# RAMPS_1_6_2.net
KiCad netlist of a schematic drawn in EAGLE
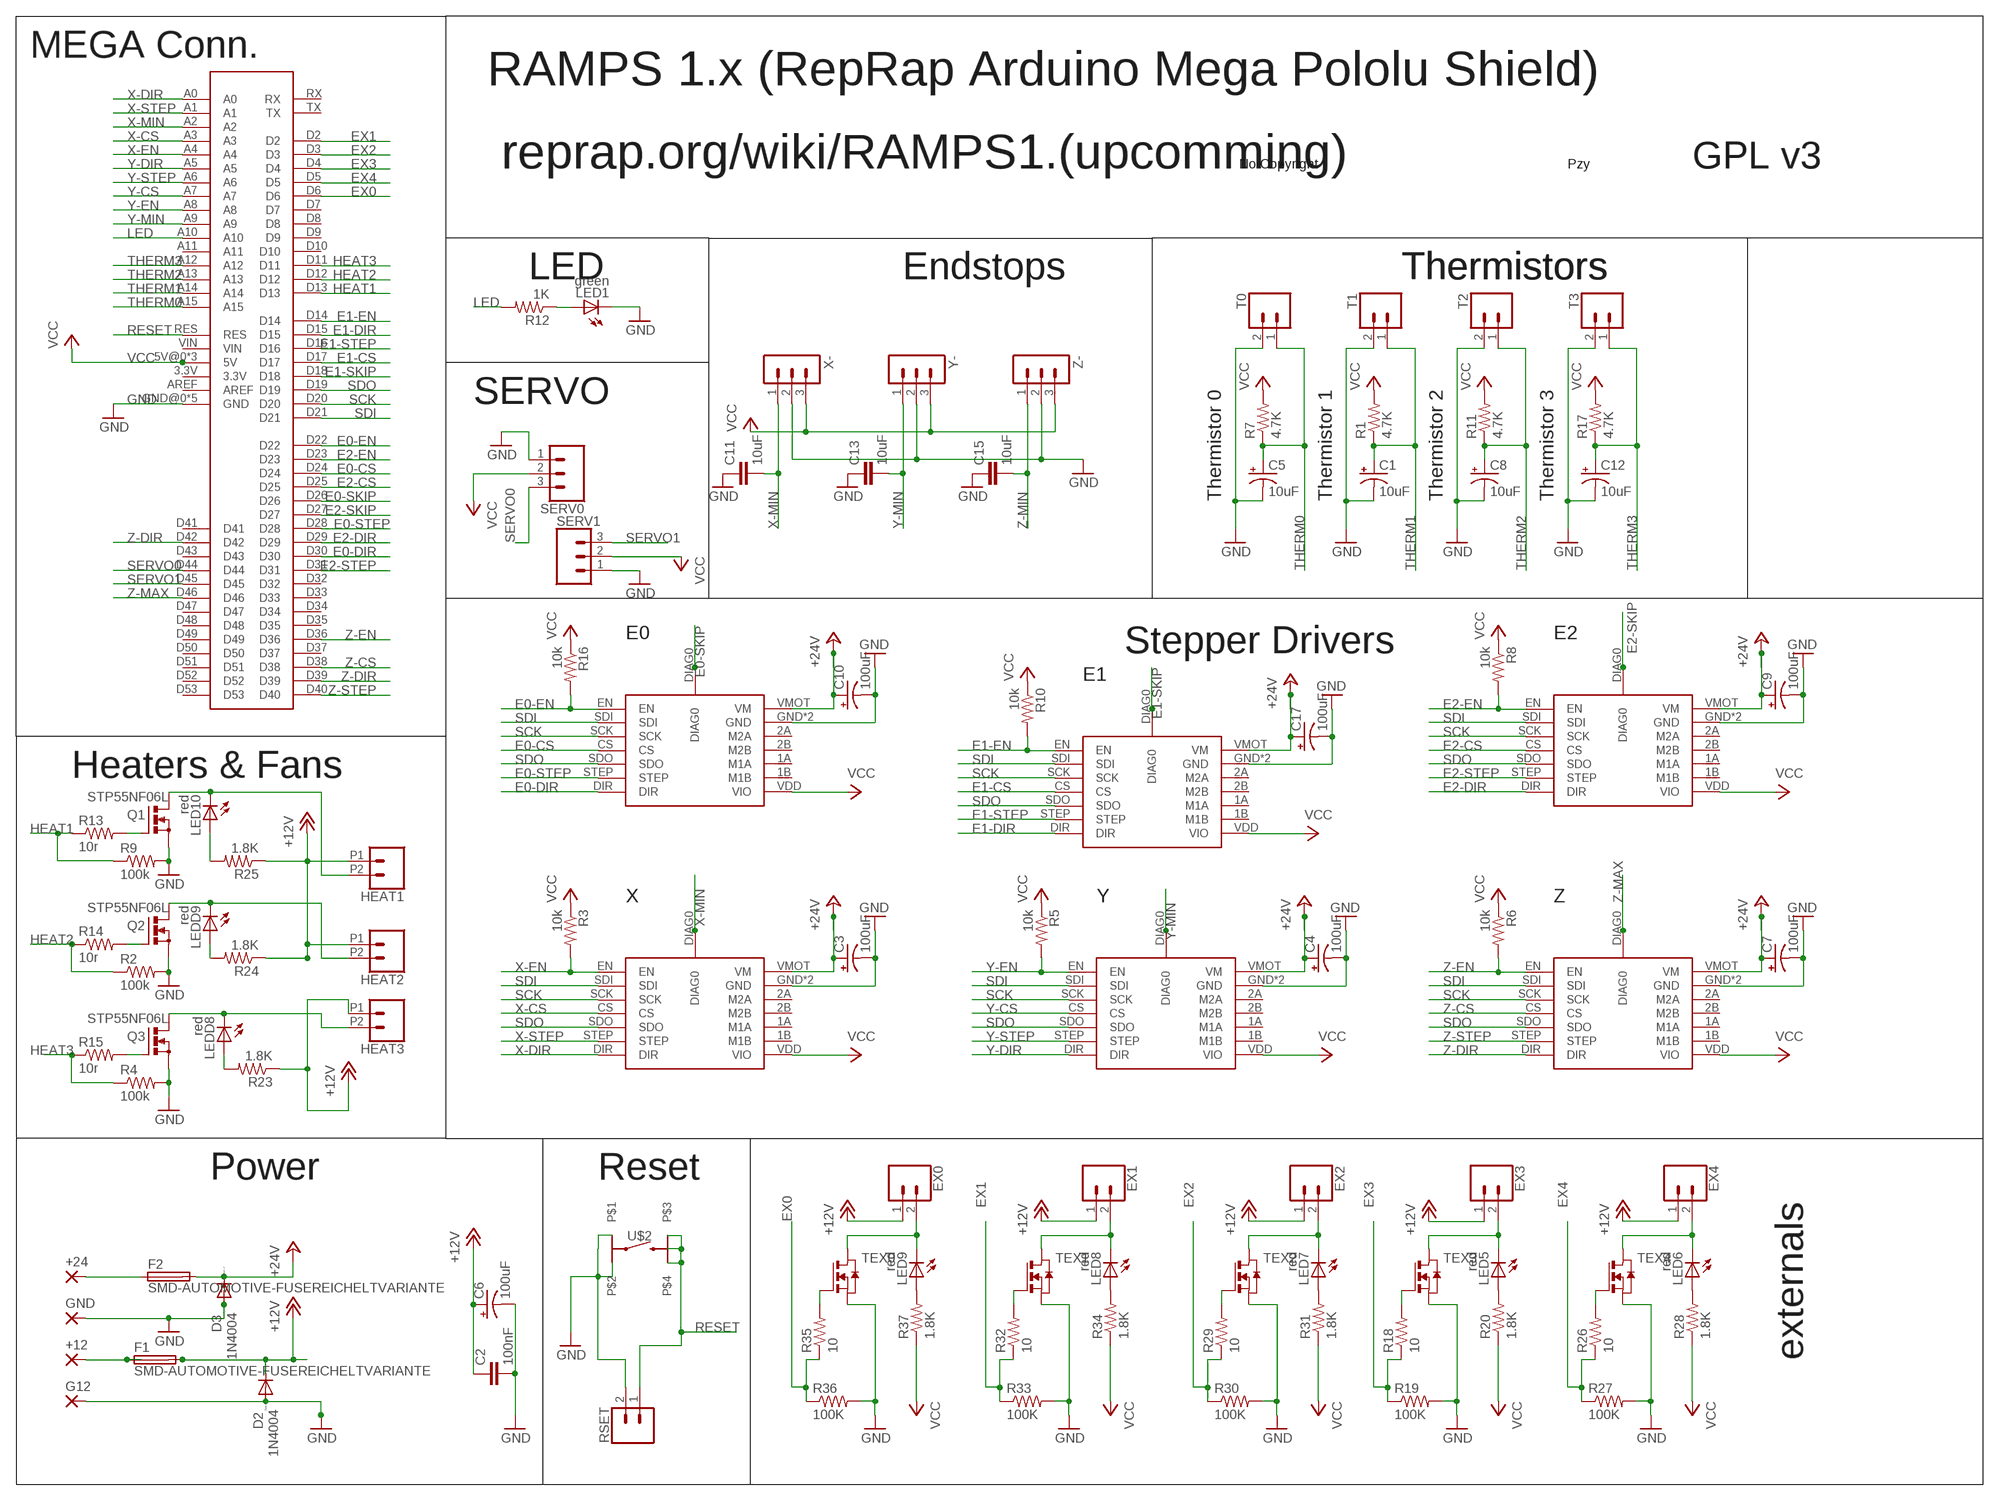
[diagram p0: schematic, sheet 1]

(export (version "E")
  (design (tool "Eeschema 10.0.6"))
  (components
    (comp (ref "+12")
      (value "2,15/1,0")
      (footprint "eagle-import:2,15_1,0")
      (libsource (lib "eagle-import") (part "2,15/1,0"))
    )
    (comp (ref "+24")
      (value "2,15/1,0")
      (footprint "eagle-import:2,15_1,0")
      (libsource (lib "eagle-import") (part "2,15/1,0"))
    )
    (comp (ref "C1")
      (value "10uF")
      (footprint "eagle-import:153CLV-0405")
      (libsource (lib "eagle-import") (part "CPOL-US153CLV-0405"))
    )
    (comp (ref "C2")
      (value "100nF")
      (footprint "eagle-import:C1206")
      (libsource (lib "eagle-import") (part "resistor_348_C-EUC1206"))
    )
    (comp (ref "C3")
      (value "100uF")
      (footprint "eagle-import:153CLV-0605")
      (libsource (lib "eagle-import") (part "CPOL-US153CLV-0605"))
    )
    (comp (ref "C4")
      (value "100uF")
      (footprint "eagle-import:153CLV-0605")
      (libsource (lib "eagle-import") (part "CPOL-US153CLV-0605"))
    )
    (comp (ref "C5")
      (value "10uF")
      (footprint "eagle-import:153CLV-0405")
      (libsource (lib "eagle-import") (part "CPOL-US153CLV-0405"))
    )
    (comp (ref "C6")
      (value "100uF")
      (footprint "eagle-import:153CLV-0605")
      (libsource (lib "eagle-import") (part "CPOL-US153CLV-0605"))
    )
    (comp (ref "C7")
      (value "100uF")
      (footprint "eagle-import:153CLV-0605")
      (libsource (lib "eagle-import") (part "CPOL-US153CLV-0605"))
    )
    (comp (ref "C8")
      (value "10uF")
      (footprint "eagle-import:153CLV-0405")
      (libsource (lib "eagle-import") (part "CPOL-US153CLV-0405"))
    )
    (comp (ref "C9")
      (value "100uF")
      (footprint "eagle-import:153CLV-0605")
      (libsource (lib "eagle-import") (part "CPOL-US153CLV-0605"))
    )
    (comp (ref "C10")
      (value "100uF")
      (footprint "eagle-import:153CLV-0605")
      (libsource (lib "eagle-import") (part "CPOL-US153CLV-0605"))
    )
    (comp (ref "C11")
      (value "10uF")
      (footprint "eagle-import:C1206")
      (libsource (lib "eagle-import") (part "C-EUC1206"))
    )
    (comp (ref "C12")
      (value "10uF")
      (footprint "eagle-import:153CLV-0405")
      (libsource (lib "eagle-import") (part "CPOL-US153CLV-0405"))
    )
    (comp (ref "C13")
      (value "10uF")
      (footprint "eagle-import:C1206")
      (libsource (lib "eagle-import") (part "C-EUC1206"))
    )
    (comp (ref "C15")
      (value "10uF")
      (footprint "eagle-import:C1206")
      (libsource (lib "eagle-import") (part "C-EUC1206"))
    )
    (comp (ref "C17")
      (value "100uF")
      (footprint "eagle-import:153CLV-0605")
      (libsource (lib "eagle-import") (part "CPOL-US153CLV-0605"))
    )
    (comp (ref "D2")
      (value "1N4004")
      (footprint "eagle-import:DO41-10")
      (libsource (lib "eagle-import") (part "1N4004"))
    )
    (comp (ref "D3")
      (value "1N4004")
      (footprint "eagle-import:DO41-10")
      (libsource (lib "eagle-import") (part "1N4004"))
    )
    (comp (ref "E0")
      (value "TMC2130DIAG")
      (footprint "eagle-import:TMC2130DIAG0")
      (libsource (lib "eagle-import") (part "TMC2130DIAG"))
    )
    (comp (ref "E1")
      (value "TMC2130DIAG")
      (footprint "eagle-import:TMC2130DIAG0")
      (libsource (lib "eagle-import") (part "TMC2130DIAG"))
    )
    (comp (ref "E2")
      (value "TMC2130DIAG")
      (footprint "eagle-import:TMC2130DIAG0")
      (libsource (lib "eagle-import") (part "TMC2130DIAG"))
    )
    (comp (ref "EX0")
      (value "CONN_02POLAR_LOCK")
      (footprint "eagle-import:MOLEX-1X2_LOCK")
      (fields (field (name "SPICEPREFIX") "B"))
      (libsource (lib "eagle-import") (part "CONN_02POLAR_LOCK"))
    )
    (comp (ref "EX1")
      (value "CONN_02POLAR_LOCK")
      (footprint "eagle-import:MOLEX-1X2_LOCK")
      (fields (field (name "SPICEPREFIX") "B"))
      (libsource (lib "eagle-import") (part "CONN_02POLAR_LOCK"))
    )
    (comp (ref "EX2")
      (value "CONN_02POLAR_LOCK")
      (footprint "eagle-import:MOLEX-1X2_LOCK")
      (fields (field (name "SPICEPREFIX") "B"))
      (libsource (lib "eagle-import") (part "CONN_02POLAR_LOCK"))
    )
    (comp (ref "EX3")
      (value "CONN_02POLAR_LOCK")
      (footprint "eagle-import:MOLEX-1X2_LOCK")
      (fields (field (name "SPICEPREFIX") "B"))
      (libsource (lib "eagle-import") (part "CONN_02POLAR_LOCK"))
    )
    (comp (ref "EX4")
      (value "CONN_02POLAR_LOCK")
      (footprint "eagle-import:MOLEX-1X2_LOCK")
      (fields (field (name "SPICEPREFIX") "B"))
      (libsource (lib "eagle-import") (part "CONN_02POLAR_LOCK"))
    )
    (comp (ref "F1")
      (value "SMD-AUTOMOTIVE-FUSEREICHELTVARIANTE")
      (footprint "eagle-import:RS-SMDFUSE")
      (libsource (lib "eagle-import") (part "SMD-AUTOMOTIVE-FUSEREICHELTVARIANTE"))
    )
    (comp (ref "F2")
      (value "SMD-AUTOMOTIVE-FUSEREICHELTVARIANTE")
      (footprint "eagle-import:RS-SMDFUSE")
      (libsource (lib "eagle-import") (part "SMD-AUTOMOTIVE-FUSEREICHELTVARIANTE"))
    )
    (comp (ref "G12")
      (value "2,15/1,0")
      (footprint "eagle-import:2,15_1,0")
      (libsource (lib "eagle-import") (part "2,15/1,0"))
    )
    (comp (ref "GND")
      (value "2,15/1,0")
      (footprint "eagle-import:2,15_1,0")
      (libsource (lib "eagle-import") (part "2,15/1,0"))
    )
    (comp (ref "HEAT1")
      (value "CONN_022.54MM_SCREWTERM")
      (footprint "eagle-import:1X02_2.54_SCREWTERM")
      (libsource (lib "eagle-import") (part "CONN_022.54MM_SCREWTERM"))
    )
    (comp (ref "HEAT2")
      (value "CONN_022.54MM_SCREWTERM")
      (footprint "eagle-import:1X02_2.54_SCREWTERM")
      (libsource (lib "eagle-import") (part "CONN_022.54MM_SCREWTERM"))
    )
    (comp (ref "HEAT3")
      (value "CONN_022.54MM_SCREWTERM")
      (footprint "eagle-import:1X02_2.54_SCREWTERM")
      (libsource (lib "eagle-import") (part "CONN_022.54MM_SCREWTERM"))
    )
    (comp (ref "LED1")
      (value "green")
      (footprint "eagle-import:CHIPLED_1206")
      (libsource (lib "eagle-import") (part "LEDCHIPLED_1206"))
    )
    (comp (ref "LED5")
      (value "red")
      (footprint "eagle-import:CHIPLED_1206")
      (fields (field (name "SPICEPREFIX") "L"))
      (libsource (lib "eagle-import") (part "LEDCHIPLED_1206"))
    )
    (comp (ref "LED6")
      (value "red")
      (footprint "eagle-import:CHIPLED_1206")
      (fields (field (name "SPICEPREFIX") "L"))
      (libsource (lib "eagle-import") (part "LEDCHIPLED_1206"))
    )
    (comp (ref "LED7")
      (value "red")
      (footprint "eagle-import:CHIPLED_1206")
      (fields (field (name "SPICEPREFIX") "L"))
      (libsource (lib "eagle-import") (part "LEDCHIPLED_1206"))
    )
    (comp (ref "LED8")
      (value "red")
      (footprint "eagle-import:CHIPLED_1206")
      (fields (field (name "SPICEPREFIX") "L"))
      (libsource (lib "eagle-import") (part "LEDCHIPLED_1206"))
    )
    (comp (ref "LED9")
      (value "red")
      (footprint "eagle-import:CHIPLED_1206")
      (fields (field (name "SPICEPREFIX") "L"))
      (libsource (lib "eagle-import") (part "LEDCHIPLED_1206"))
    )
    (comp (ref "LED10")
      (value "red")
      (footprint "eagle-import:CHIPLED_1206")
      (libsource (lib "eagle-import") (part "LEDCHIPLED_1206"))
    )
    (comp (ref "LEDD8")
      (value "red")
      (footprint "eagle-import:CHIPLED_1206")
      (libsource (lib "eagle-import") (part "LEDCHIPLED_1206"))
    )
    (comp (ref "LEDD9")
      (value "red")
      (footprint "eagle-import:CHIPLED_1206")
      (libsource (lib "eagle-import") (part "LEDCHIPLED_1206"))
    )
    (comp (ref "Q1")
      (value "STP55NF06L")
      (footprint "eagle-import:TO220BV")
      (libsource (lib "eagle-import") (part "IRF512"))
    )
    (comp (ref "Q2")
      (value "STP55NF06L")
      (footprint "eagle-import:TO220BV")
      (libsource (lib "eagle-import") (part "IRF512"))
    )
    (comp (ref "Q3")
      (value "STP55NF06L")
      (footprint "eagle-import:TO220BV")
      (libsource (lib "eagle-import") (part "IRF512"))
    )
    (comp (ref "R1")
      (value "4.7K")
      (footprint "eagle-import:R1206")
      (libsource (lib "eagle-import") (part "R-US_R1206"))
    )
    (comp (ref "R2")
      (value "100k")
      (footprint "eagle-import:R1206")
      (libsource (lib "eagle-import") (part "R-US_R1206"))
    )
    (comp (ref "R3")
      (value "10k")
      (footprint "eagle-import:R1206")
      (libsource (lib "eagle-import") (part "R-US_R1206"))
    )
    (comp (ref "R4")
      (value "100k")
      (footprint "eagle-import:R1206")
      (libsource (lib "eagle-import") (part "R-US_R1206"))
    )
    (comp (ref "R5")
      (value "10k")
      (footprint "eagle-import:R1206")
      (libsource (lib "eagle-import") (part "R-US_R1206"))
    )
    (comp (ref "R6")
      (value "10k")
      (footprint "eagle-import:R1206")
      (libsource (lib "eagle-import") (part "R-US_R1206"))
    )
    (comp (ref "R7")
      (value "4.7K")
      (footprint "eagle-import:R1206")
      (libsource (lib "eagle-import") (part "R-US_R1206"))
    )
    (comp (ref "R8")
      (value "10k")
      (footprint "eagle-import:R1206")
      (libsource (lib "eagle-import") (part "R-US_R1206"))
    )
    (comp (ref "R9")
      (value "100k")
      (footprint "eagle-import:R1206")
      (libsource (lib "eagle-import") (part "R-US_R1206"))
    )
    (comp (ref "R10")
      (value "10k")
      (footprint "eagle-import:R1206")
      (libsource (lib "eagle-import") (part "R-US_R1206"))
    )
    (comp (ref "R11")
      (value "4.7K")
      (footprint "eagle-import:R1206")
      (libsource (lib "eagle-import") (part "R-US_R1206"))
    )
    (comp (ref "R12")
      (value "1K")
      (footprint "eagle-import:R1206")
      (libsource (lib "eagle-import") (part "R-US_R1206"))
    )
    (comp (ref "R13")
      (value "10r")
      (footprint "eagle-import:R1206")
      (libsource (lib "eagle-import") (part "resistor_348_R-US_R1206"))
    )
    (comp (ref "R14")
      (value "10r")
      (footprint "eagle-import:R1206")
      (libsource (lib "eagle-import") (part "resistor_348_R-US_R1206"))
    )
    (comp (ref "R15")
      (value "10r")
      (footprint "eagle-import:R1206")
      (libsource (lib "eagle-import") (part "resistor_348_R-US_R1206"))
    )
    (comp (ref "R16")
      (value "10k")
      (footprint "eagle-import:R1206")
      (libsource (lib "eagle-import") (part "R-US_R1206"))
    )
    (comp (ref "R17")
      (value "4.7K")
      (footprint "eagle-import:R1206")
      (libsource (lib "eagle-import") (part "R-US_R1206"))
    )
    (comp (ref "R18")
      (value "10")
      (footprint "eagle-import:R1206")
      (fields (field (name "SPICEPREFIX") "R"))
      (libsource (lib "eagle-import") (part "resistor_348_R-US_R1206"))
    )
    (comp (ref "R19")
      (value "100K")
      (footprint "eagle-import:R1206")
      (fields (field (name "SPICEPREFIX") "L"))
      (libsource (lib "eagle-import") (part "resistor_348_R-US_R1206"))
    )
    (comp (ref "R20")
      (value "1.8K")
      (footprint "eagle-import:R1206")
      (fields (field (name "SPICEPREFIX") "R"))
      (libsource (lib "eagle-import") (part "resistor_348_R-US_R1206"))
    )
    (comp (ref "R23")
      (value "1.8K")
      (footprint "eagle-import:R1206")
      (libsource (lib "eagle-import") (part "R-US_R1206"))
    )
    (comp (ref "R24")
      (value "1.8K")
      (footprint "eagle-import:R1206")
      (libsource (lib "eagle-import") (part "R-US_R1206"))
    )
    (comp (ref "R25")
      (value "1.8K")
      (footprint "eagle-import:R1206")
      (libsource (lib "eagle-import") (part "R-US_R1206"))
    )
    (comp (ref "R26")
      (value "10")
      (footprint "eagle-import:R1206")
      (fields (field (name "SPICEPREFIX") "R"))
      (libsource (lib "eagle-import") (part "resistor_348_R-US_R1206"))
    )
    (comp (ref "R27")
      (value "100K")
      (footprint "eagle-import:R1206")
      (fields (field (name "SPICEPREFIX") "R"))
      (libsource (lib "eagle-import") (part "resistor_348_R-US_R1206"))
    )
    (comp (ref "R28")
      (value "1.8K")
      (footprint "eagle-import:R1206")
      (fields (field (name "SPICEPREFIX") "R"))
      (libsource (lib "eagle-import") (part "resistor_348_R-US_R1206"))
    )
    (comp (ref "R29")
      (value "10")
      (footprint "eagle-import:R1206")
      (fields (field (name "SPICEPREFIX") "R"))
      (libsource (lib "eagle-import") (part "resistor_348_R-US_R1206"))
    )
    (comp (ref "R30")
      (value "100K")
      (footprint "eagle-import:R1206")
      (fields (field (name "SPICEPREFIX") "R"))
      (libsource (lib "eagle-import") (part "resistor_348_R-US_R1206"))
    )
    (comp (ref "R31")
      (value "1.8K")
      (footprint "eagle-import:R1206")
      (fields (field (name "SPICEPREFIX") "R"))
      (libsource (lib "eagle-import") (part "resistor_348_R-US_R1206"))
    )
    (comp (ref "R32")
      (value "10")
      (footprint "eagle-import:R1206")
      (fields (field (name "SPICEPREFIX") "R"))
      (libsource (lib "eagle-import") (part "resistor_348_R-US_R1206"))
    )
    (comp (ref "R33")
      (value "100K")
      (footprint "eagle-import:R1206")
      (fields (field (name "SPICEPREFIX") "R"))
      (libsource (lib "eagle-import") (part "resistor_348_R-US_R1206"))
    )
    (comp (ref "R34")
      (value "1.8K")
      (footprint "eagle-import:R1206")
      (fields (field (name "SPICEPREFIX") "R"))
      (libsource (lib "eagle-import") (part "resistor_348_R-US_R1206"))
    )
    (comp (ref "R35")
      (value "10")
      (footprint "eagle-import:R1206")
      (fields (field (name "SPICEPREFIX") "R"))
      (libsource (lib "eagle-import") (part "resistor_348_R-US_R1206"))
    )
    (comp (ref "R36")
      (value "100K")
      (footprint "eagle-import:R1206")
      (fields (field (name "SPICEPREFIX") "R"))
      (libsource (lib "eagle-import") (part "resistor_348_R-US_R1206"))
    )
    (comp (ref "R37")
      (value "1.8K")
      (footprint "eagle-import:R1206")
      (fields (field (name "SPICEPREFIX") "R"))
      (libsource (lib "eagle-import") (part "resistor_348_R-US_R1206"))
    )
    (comp (ref "RSET")
      (value "CONN_02POLAR_LOCK")
      (footprint "eagle-import:MOLEX-1X2_LOCK")
      (fields (field (name "SPICEPREFIX") "B"))
      (libsource (lib "eagle-import") (part "CONN_02POLAR_LOCK"))
    )
    (comp (ref "SERV0")
      (value "CONN_03")
      (footprint "eagle-import:1X03")
      (libsource (lib "eagle-import") (part "CONN_03"))
    )
    (comp (ref "SERV1")
      (value "CONN_03")
      (footprint "eagle-import:1X03")
      (libsource (lib "eagle-import") (part "CONN_03"))
    )
    (comp (ref "T0")
      (value "CONN_02LOCK")
      (footprint "eagle-import:1X02_LOCK")
      (libsource (lib "eagle-import") (part "CONN_02LOCK"))
    )
    (comp (ref "T1")
      (value "CONN_02LOCK")
      (footprint "eagle-import:1X02_LOCK")
      (libsource (lib "eagle-import") (part "CONN_02LOCK"))
    )
    (comp (ref "T2")
      (value "CONN_02LOCK")
      (footprint "eagle-import:1X02_LOCK")
      (libsource (lib "eagle-import") (part "CONN_02LOCK"))
    )
    (comp (ref "T3")
      (value "CONN_02LOCK")
      (footprint "eagle-import:1X02_LOCK")
      (libsource (lib "eagle-import") (part "CONN_02LOCK"))
    )
    (comp (ref "TEX0")
      (value "NMOSSOT223")
      (footprint "eagle-import:SOT223")
      (fields (field (name "SPICEPREFIX") "J"))
      (libsource (lib "eagle-import") (part "NMOSSOT223"))
    )
    (comp (ref "TEX1")
      (value "NMOSSOT223")
      (footprint "eagle-import:SOT223")
      (fields (field (name "SPICEPREFIX") "J"))
      (libsource (lib "eagle-import") (part "NMOSSOT223"))
    )
    (comp (ref "TEX2")
      (value "NMOSSOT223")
      (footprint "eagle-import:SOT223")
      (fields (field (name "SPICEPREFIX") "J"))
      (libsource (lib "eagle-import") (part "NMOSSOT223"))
    )
    (comp (ref "TEX3")
      (value "NMOSSOT223")
      (footprint "eagle-import:SOT223")
      (fields (field (name "SPICEPREFIX") "J"))
      (libsource (lib "eagle-import") (part "NMOSSOT223"))
    )
    (comp (ref "TEX4")
      (value "NMOSSOT223")
      (footprint "eagle-import:SOT223")
      (fields (field (name "SPICEPREFIX") "J"))
      (libsource (lib "eagle-import") (part "NMOSSOT223"))
    )
    (comp (ref "U$1")
      (value "ARDUINOSHIELD")
      (footprint "eagle-import:REPRAPJR_ARDUINO_MEGA_SHIELD")
      (libsource (lib "eagle-import") (part "ARDUINOSHIELD"))
    )
    (comp (ref "U$2")
      (value "RS-TASTER")
      (footprint "eagle-import:RS-SWITCH")
      (libsource (lib "eagle-import") (part "RS-TASTER"))
    )
    (comp (ref "X")
      (value "TMC2130DIAG")
      (footprint "eagle-import:TMC2130DIAG0")
      (libsource (lib "eagle-import") (part "TMC2130DIAG"))
    )
    (comp (ref "X-")
      (value "3PIN-HEADER")
      (footprint "eagle-import:3PIN-HEADER")
      (libsource (lib "eagle-import") (part "3PIN-HEADER"))
    )
    (comp (ref "Y")
      (value "TMC2130DIAG")
      (footprint "eagle-import:TMC2130DIAG0")
      (libsource (lib "eagle-import") (part "TMC2130DIAG"))
    )
    (comp (ref "Y-")
      (value "3PIN-HEADER")
      (footprint "eagle-import:3PIN-HEADER")
      (libsource (lib "eagle-import") (part "3PIN-HEADER"))
    )
    (comp (ref "Z")
      (value "TMC2130DIAG")
      (footprint "eagle-import:TMC2130DIAG0")
      (libsource (lib "eagle-import") (part "TMC2130DIAG"))
    )
    (comp (ref "Z-")
      (value "3PIN-HEADER")
      (footprint "eagle-import:3PIN-HEADER")
      (libsource (lib "eagle-import") (part "3PIN-HEADER"))
    )
  )
  (nets
    (net (code "1") (name "+12V") (class "Default")
      (node (ref "C2") (pin "1") (pinfunction "1_1") (pintype "passive"))
      (node (ref "C6") (pin "+") (pinfunction "+_+") (pintype "passive"))
      (node (ref "D2") (pin "C") (pinfunction "C_C") (pintype "passive"))
      (node (ref "EX0") (pin "1") (pinfunction "1_1") (pintype "passive"))
      (node (ref "EX1") (pin "1") (pinfunction "1_1") (pintype "passive"))
      (node (ref "EX2") (pin "1") (pinfunction "1_1") (pintype "passive"))
      (node (ref "EX3") (pin "1") (pinfunction "1_1") (pintype "passive"))
      (node (ref "EX4") (pin "1") (pinfunction "1_1") (pintype "passive"))
      (node (ref "F1") (pin "P$5") (pinfunction "2_P$5") (pintype "passive"))
      (node (ref "F1") (pin "P$6") (pinfunction "2_P$6") (pintype "passive"))
      (node (ref "F1") (pin "P$7") (pinfunction "2_P$7") (pintype "passive"))
      (node (ref "F1") (pin "P$8") (pinfunction "2_P$8") (pintype "passive"))
      (node (ref "HEAT1") (pin "P1") (pinfunction "1_P1") (pintype "passive"))
      (node (ref "HEAT2") (pin "P1") (pinfunction "1_P1") (pintype "passive"))
      (node (ref "HEAT3") (pin "P1") (pinfunction "1_P1") (pintype "passive"))
      (node (ref "R23") (pin "1") (pinfunction "1_1") (pintype "passive"))
      (node (ref "R24") (pin "1") (pinfunction "1_1") (pintype "passive"))
      (node (ref "R25") (pin "1") (pinfunction "1_1") (pintype "passive"))
    )
    (net (code "2") (name "+24V") (class "Default")
      (node (ref "C10") (pin "+") (pinfunction "+_+") (pintype "passive"))
      (node (ref "C17") (pin "+") (pinfunction "+_+") (pintype "passive"))
      (node (ref "C3") (pin "+") (pinfunction "+_+") (pintype "passive"))
      (node (ref "C4") (pin "+") (pinfunction "+_+") (pintype "passive"))
      (node (ref "C7") (pin "+") (pinfunction "+_+") (pintype "passive"))
      (node (ref "C9") (pin "+") (pinfunction "+_+") (pintype "passive"))
      (node (ref "D3") (pin "C") (pinfunction "C_C") (pintype "passive"))
      (node (ref "E0") (pin "VMOT") (pinfunction "VM_VMOT") (pintype "bidirectional"))
      (node (ref "E1") (pin "VMOT") (pinfunction "VM_VMOT") (pintype "bidirectional"))
      (node (ref "E2") (pin "VMOT") (pinfunction "VM_VMOT") (pintype "bidirectional"))
      (node (ref "F2") (pin "P$5") (pinfunction "2_P$5") (pintype "passive"))
      (node (ref "F2") (pin "P$6") (pinfunction "2_P$6") (pintype "passive"))
      (node (ref "F2") (pin "P$7") (pinfunction "2_P$7") (pintype "passive"))
      (node (ref "F2") (pin "P$8") (pinfunction "2_P$8") (pintype "passive"))
      (node (ref "X") (pin "VMOT") (pinfunction "VM_VMOT") (pintype "bidirectional"))
      (node (ref "Y") (pin "VMOT") (pinfunction "VM_VMOT") (pintype "bidirectional"))
      (node (ref "Z") (pin "VMOT") (pinfunction "VM_VMOT") (pintype "bidirectional"))
    )
    (net (code "3") (name "/3.3V") (class "Default")
      (node (ref "U$1") (pin "3.3V") (pinfunction "3.3V_3.3V") (pintype "power_in"))
    )
    (net (code "4") (name "/AREF") (class "Default")
      (node (ref "U$1") (pin "AREF") (pinfunction "AREF_AREF") (pintype "power_in"))
    )
    (net (code "5") (name "/E0-CS") (class "Default")
      (node (ref "E0") (pin "CS") (pinfunction "CS_CS") (pintype "bidirectional"))
      (node (ref "U$1") (pin "D24") (pinfunction "D24_D24") (pintype "bidirectional"))
    )
    (net (code "6") (name "/E0-DIR") (class "Default")
      (node (ref "E0") (pin "DIR") (pinfunction "DIR_DIR") (pintype "bidirectional"))
      (node (ref "U$1") (pin "D30") (pinfunction "D30_D30") (pintype "bidirectional"))
    )
    (net (code "7") (name "/E0-EN") (class "Default")
      (node (ref "E0") (pin "EN") (pinfunction "EN_EN") (pintype "bidirectional"))
      (node (ref "R16") (pin "2") (pinfunction "2_2") (pintype "passive"))
      (node (ref "U$1") (pin "D22") (pinfunction "D22_D22") (pintype "bidirectional"))
    )
    (net (code "8") (name "/E0-SKIP") (class "Default")
      (node (ref "E0") (pin "DIAG0") (pinfunction "DIAG0_DIAG0") (pintype "bidirectional"))
      (node (ref "U$1") (pin "D26") (pinfunction "D26_D26") (pintype "bidirectional"))
    )
    (net (code "9") (name "/E0-STEP") (class "Default")
      (node (ref "E0") (pin "STEP") (pinfunction "STEP_STEP") (pintype "bidirectional"))
      (node (ref "U$1") (pin "D28") (pinfunction "D28_D28") (pintype "bidirectional"))
    )
    (net (code "10") (name "/E1-CS") (class "Default")
      (node (ref "E1") (pin "CS") (pinfunction "CS_CS") (pintype "bidirectional"))
      (node (ref "U$1") (pin "D17") (pinfunction "D17_D17") (pintype "bidirectional"))
    )
    (net (code "11") (name "/E1-DIR") (class "Default")
      (node (ref "E1") (pin "DIR") (pinfunction "DIR_DIR") (pintype "bidirectional"))
      (node (ref "U$1") (pin "D15") (pinfunction "D15_D15") (pintype "bidirectional"))
    )
    (net (code "12") (name "/E1-EN") (class "Default")
      (node (ref "E1") (pin "EN") (pinfunction "EN_EN") (pintype "bidirectional"))
      (node (ref "R10") (pin "2") (pinfunction "2_2") (pintype "passive"))
      (node (ref "U$1") (pin "D14") (pinfunction "D14_D14") (pintype "bidirectional"))
    )
    (net (code "13") (name "/E1-SKIP") (class "Default")
      (node (ref "E1") (pin "DIAG0") (pinfunction "DIAG0_DIAG0") (pintype "bidirectional"))
      (node (ref "U$1") (pin "D18") (pinfunction "D18_D18") (pintype "bidirectional"))
    )
    (net (code "14") (name "/E1-STEP") (class "Default")
      (node (ref "E1") (pin "STEP") (pinfunction "STEP_STEP") (pintype "bidirectional"))
      (node (ref "U$1") (pin "D16") (pinfunction "D16_D16") (pintype "bidirectional"))
    )
    (net (code "15") (name "/E2-CS") (class "Default")
      (node (ref "E2") (pin "CS") (pinfunction "CS_CS") (pintype "bidirectional"))
      (node (ref "U$1") (pin "D25") (pinfunction "D25_D25") (pintype "bidirectional"))
    )
    (net (code "16") (name "/E2-DIR") (class "Default")
      (node (ref "E2") (pin "DIR") (pinfunction "DIR_DIR") (pintype "bidirectional"))
      (node (ref "U$1") (pin "D29") (pinfunction "D29_D29") (pintype "bidirectional"))
    )
    (net (code "17") (name "/E2-EN") (class "Default")
      (node (ref "E2") (pin "EN") (pinfunction "EN_EN") (pintype "bidirectional"))
      (node (ref "R8") (pin "2") (pinfunction "2_2") (pintype "passive"))
      (node (ref "U$1") (pin "D23") (pinfunction "D23_D23") (pintype "bidirectional"))
    )
    (net (code "18") (name "/E2-SKIP") (class "Default")
      (node (ref "E2") (pin "DIAG0") (pinfunction "DIAG0_DIAG0") (pintype "bidirectional"))
      (node (ref "U$1") (pin "D27") (pinfunction "D27_D27") (pintype "bidirectional"))
    )
    (net (code "19") (name "/E2-STEP") (class "Default")
      (node (ref "E2") (pin "STEP") (pinfunction "STEP_STEP") (pintype "bidirectional"))
      (node (ref "U$1") (pin "D31") (pinfunction "D31_D31") (pintype "bidirectional"))
    )
    (net (code "20") (name "/EX0") (class "Default")
      (node (ref "R35") (pin "1") (pinfunction "1_1") (pintype "passive"))
      (node (ref "R36") (pin "1") (pinfunction "1_1") (pintype "passive"))
      (node (ref "U$1") (pin "D6") (pinfunction "D6_D6") (pintype "bidirectional"))
    )
    (net (code "21") (name "/EX1") (class "Default")
      (node (ref "R32") (pin "1") (pinfunction "1_1") (pintype "passive"))
      (node (ref "R33") (pin "1") (pinfunction "1_1") (pintype "passive"))
      (node (ref "U$1") (pin "D2") (pinfunction "D2_D2") (pintype "bidirectional"))
    )
    (net (code "22") (name "/EX2") (class "Default")
      (node (ref "R29") (pin "1") (pinfunction "1_1") (pintype "passive"))
      (node (ref "R30") (pin "1") (pinfunction "1_1") (pintype "passive"))
      (node (ref "U$1") (pin "D3") (pinfunction "D3_D3") (pintype "bidirectional"))
    )
    (net (code "23") (name "/EX3") (class "Default")
      (node (ref "R18") (pin "1") (pinfunction "1_1") (pintype "passive"))
      (node (ref "R19") (pin "1") (pinfunction "1_1") (pintype "passive"))
      (node (ref "U$1") (pin "D4") (pinfunction "D4_D4") (pintype "bidirectional"))
    )
    (net (code "24") (name "/EX4") (class "Default")
      (node (ref "R26") (pin "1") (pinfunction "1_1") (pintype "passive"))
      (node (ref "R27") (pin "1") (pinfunction "1_1") (pintype "passive"))
      (node (ref "U$1") (pin "D5") (pinfunction "D5_D5") (pintype "bidirectional"))
    )
    (net (code "25") (name "/HEAT1") (class "Default")
      (node (ref "R13") (pin "1") (pinfunction "1_1") (pintype "passive"))
      (node (ref "R9") (pin "1") (pinfunction "1_1") (pintype "passive"))
      (node (ref "U$1") (pin "D13") (pinfunction "D13_D13") (pintype "bidirectional"))
    )
    (net (code "26") (name "/HEAT2") (class "Default")
      (node (ref "R14") (pin "1") (pinfunction "1_1") (pintype "passive"))
      (node (ref "R2") (pin "1") (pinfunction "1_1") (pintype "passive"))
      (node (ref "U$1") (pin "D12") (pinfunction "D12_D12") (pintype "bidirectional"))
    )
    (net (code "27") (name "/HEAT3") (class "Default")
      (node (ref "R15") (pin "1") (pinfunction "1_1") (pintype "passive"))
      (node (ref "R4") (pin "1") (pinfunction "1_1") (pintype "passive"))
      (node (ref "U$1") (pin "D11") (pinfunction "D11_D11") (pintype "bidirectional"))
    )
    (net (code "28") (name "/LED") (class "Default")
      (node (ref "R12") (pin "2") (pinfunction "2_2") (pintype "passive"))
      (node (ref "U$1") (pin "A10") (pinfunction "A10_A10") (pintype "bidirectional"))
    )
    (net (code "29") (name "/RESET") (class "Default")
      (node (ref "RSET") (pin "1") (pinfunction "1_1") (pintype "passive"))
      (node (ref "U$1") (pin "RES") (pinfunction "RES_RES") (pintype "bidirectional"))
      (node (ref "U$2") (pin "P$3") (pinfunction "P$3_P$3") (pintype "bidirectional"))
      (node (ref "U$2") (pin "P$4") (pinfunction "P$4_P$4") (pintype "bidirectional"))
    )
    (net (code "30") (name "/SCK") (class "Default")
      (node (ref "E0") (pin "SCK") (pinfunction "SCK_SCK") (pintype "bidirectional"))
      (node (ref "E1") (pin "SCK") (pinfunction "SCK_SCK") (pintype "bidirectional"))
      (node (ref "E2") (pin "SCK") (pinfunction "SCK_SCK") (pintype "bidirectional"))
      (node (ref "U$1") (pin "D20") (pinfunction "D20_D20") (pintype "bidirectional"))
      (node (ref "X") (pin "SCK") (pinfunction "SCK_SCK") (pintype "bidirectional"))
      (node (ref "Y") (pin "SCK") (pinfunction "SCK_SCK") (pintype "bidirectional"))
      (node (ref "Z") (pin "SCK") (pinfunction "SCK_SCK") (pintype "bidirectional"))
    )
    (net (code "31") (name "/SDI") (class "Default")
      (node (ref "E0") (pin "SDI") (pinfunction "SDI_SDI") (pintype "bidirectional"))
      (node (ref "E1") (pin "SDI") (pinfunction "SDI_SDI") (pintype "bidirectional"))
      (node (ref "E2") (pin "SDI") (pinfunction "SDI_SDI") (pintype "bidirectional"))
      (node (ref "U$1") (pin "D21") (pinfunction "D21_D21") (pintype "bidirectional"))
      (node (ref "X") (pin "SDI") (pinfunction "SDI_SDI") (pintype "bidirectional"))
      (node (ref "Y") (pin "SDI") (pinfunction "SDI_SDI") (pintype "bidirectional"))
      (node (ref "Z") (pin "SDI") (pinfunction "SDI_SDI") (pintype "bidirectional"))
    )
    (net (code "32") (name "/SDO") (class "Default")
      (node (ref "E0") (pin "SDO") (pinfunction "SDO_SDO") (pintype "bidirectional"))
      (node (ref "E1") (pin "SDO") (pinfunction "SDO_SDO") (pintype "bidirectional"))
      (node (ref "E2") (pin "SDO") (pinfunction "SDO_SDO") (pintype "bidirectional"))
      (node (ref "U$1") (pin "D19") (pinfunction "D19_D19") (pintype "bidirectional"))
      (node (ref "X") (pin "SDO") (pinfunction "SDO_SDO") (pintype "bidirectional"))
      (node (ref "Y") (pin "SDO") (pinfunction "SDO_SDO") (pintype "bidirectional"))
      (node (ref "Z") (pin "SDO") (pinfunction "SDO_SDO") (pintype "bidirectional"))
    )
    (net (code "33") (name "/SERVO0") (class "Default")
      (node (ref "SERV0") (pin "3") (pinfunction "3_3") (pintype "passive"))
      (node (ref "U$1") (pin "D44") (pinfunction "D44_D44") (pintype "bidirectional"))
    )
    (net (code "34") (name "/SERVO1") (class "Default")
      (node (ref "SERV1") (pin "3") (pinfunction "3_3") (pintype "passive"))
      (node (ref "U$1") (pin "D45") (pinfunction "D45_D45") (pintype "bidirectional"))
    )
    (net (code "35") (name "/THERM0") (class "Default")
      (node (ref "C5") (pin "+") (pinfunction "+_+") (pintype "passive"))
      (node (ref "R7") (pin "1") (pinfunction "1_1") (pintype "passive"))
      (node (ref "T0") (pin "1") (pinfunction "1_1") (pintype "passive"))
      (node (ref "U$1") (pin "A15") (pinfunction "A15_A15") (pintype "bidirectional"))
    )
    (net (code "36") (name "/THERM1") (class "Default")
      (node (ref "C1") (pin "+") (pinfunction "+_+") (pintype "passive"))
      (node (ref "R1") (pin "1") (pinfunction "1_1") (pintype "passive"))
      (node (ref "T1") (pin "1") (pinfunction "1_1") (pintype "passive"))
      (node (ref "U$1") (pin "A14") (pinfunction "A14_A14") (pintype "bidirectional"))
    )
    (net (code "37") (name "/THERM2") (class "Default")
      (node (ref "C8") (pin "+") (pinfunction "+_+") (pintype "passive"))
      (node (ref "R11") (pin "1") (pinfunction "1_1") (pintype "passive"))
      (node (ref "T2") (pin "1") (pinfunction "1_1") (pintype "passive"))
      (node (ref "U$1") (pin "A13") (pinfunction "A13_A13") (pintype "bidirectional"))
    )
    (net (code "38") (name "/THERM3") (class "Default")
      (node (ref "C12") (pin "+") (pinfunction "+_+") (pintype "passive"))
      (node (ref "R17") (pin "1") (pinfunction "1_1") (pintype "passive"))
      (node (ref "T3") (pin "1") (pinfunction "1_1") (pintype "passive"))
      (node (ref "U$1") (pin "A12") (pinfunction "A12_A12") (pintype "bidirectional"))
    )
    (net (code "39") (name "/X-CS") (class "Default")
      (node (ref "U$1") (pin "A3") (pinfunction "A3_A3") (pintype "bidirectional"))
      (node (ref "X") (pin "CS") (pinfunction "CS_CS") (pintype "bidirectional"))
    )
    (net (code "40") (name "/X-DIR") (class "Default")
      (node (ref "U$1") (pin "A0") (pinfunction "A0_A0") (pintype "bidirectional"))
      (node (ref "X") (pin "DIR") (pinfunction "DIR_DIR") (pintype "bidirectional"))
    )
    (net (code "41") (name "/X-EN") (class "Default")
      (node (ref "R3") (pin "2") (pinfunction "2_2") (pintype "passive"))
      (node (ref "U$1") (pin "A4") (pinfunction "A4_A4") (pintype "bidirectional"))
      (node (ref "X") (pin "EN") (pinfunction "EN_EN") (pintype "bidirectional"))
    )
    (net (code "42") (name "/X-MIN") (class "Default")
      (node (ref "C11") (pin "2") (pinfunction "2_2") (pintype "passive"))
      (node (ref "U$1") (pin "A2") (pinfunction "A2_A2") (pintype "bidirectional"))
      (node (ref "X") (pin "DIAG0") (pinfunction "DIAG0_DIAG0") (pintype "bidirectional"))
      (node (ref "X-") (pin "1") (pinfunction "1_1") (pintype "passive"))
    )
    (net (code "43") (name "/X-STEP") (class "Default")
      (node (ref "U$1") (pin "A1") (pinfunction "A1_A1") (pintype "bidirectional"))
      (node (ref "X") (pin "STEP") (pinfunction "STEP_STEP") (pintype "bidirectional"))
    )
    (net (code "44") (name "/Y-CS") (class "Default")
      (node (ref "U$1") (pin "A7") (pinfunction "A7_A7") (pintype "bidirectional"))
      (node (ref "Y") (pin "CS") (pinfunction "CS_CS") (pintype "bidirectional"))
    )
    (net (code "45") (name "/Y-DIR") (class "Default")
      (node (ref "U$1") (pin "A5") (pinfunction "A5_A5") (pintype "bidirectional"))
      (node (ref "Y") (pin "DIR") (pinfunction "DIR_DIR") (pintype "bidirectional"))
    )
    (net (code "46") (name "/Y-EN") (class "Default")
      (node (ref "R5") (pin "2") (pinfunction "2_2") (pintype "passive"))
      (node (ref "U$1") (pin "A8") (pinfunction "A8_A8") (pintype "bidirectional"))
      (node (ref "Y") (pin "EN") (pinfunction "EN_EN") (pintype "bidirectional"))
    )
    (net (code "47") (name "/Y-MIN") (class "Default")
      (node (ref "C13") (pin "2") (pinfunction "2_2") (pintype "passive"))
      (node (ref "U$1") (pin "A9") (pinfunction "A9_A9") (pintype "bidirectional"))
      (node (ref "Y") (pin "DIAG0") (pinfunction "DIAG0_DIAG0") (pintype "bidirectional"))
      (node (ref "Y-") (pin "1") (pinfunction "1_1") (pintype "passive"))
    )
    (net (code "48") (name "/Y-STEP") (class "Default")
      (node (ref "U$1") (pin "A6") (pinfunction "A6_A6") (pintype "bidirectional"))
      (node (ref "Y") (pin "STEP") (pinfunction "STEP_STEP") (pintype "bidirectional"))
    )
    (net (code "49") (name "/Z-CS") (class "Default")
      (node (ref "U$1") (pin "D38") (pinfunction "D38_D38") (pintype "bidirectional"))
      (node (ref "Z") (pin "CS") (pinfunction "CS_CS") (pintype "bidirectional"))
    )
    (net (code "50") (name "/Z-DIR") (class "Default")
      (node (ref "U$1") (pin "D39") (pinfunction "D39_D39") (pintype "bidirectional"))
      (node (ref "U$1") (pin "D42") (pinfunction "D42_D42") (pintype "bidirectional"))
      (node (ref "Z") (pin "DIR") (pinfunction "DIR_DIR") (pintype "bidirectional"))
    )
    (net (code "51") (name "/Z-EN") (class "Default")
      (node (ref "R6") (pin "2") (pinfunction "2_2") (pintype "passive"))
      (node (ref "U$1") (pin "D36") (pinfunction "D36_D36") (pintype "bidirectional"))
      (node (ref "Z") (pin "EN") (pinfunction "EN_EN") (pintype "bidirectional"))
    )
    (net (code "52") (name "/Z-MAX") (class "Default")
      (node (ref "U$1") (pin "D46") (pinfunction "D46_D46") (pintype "bidirectional"))
      (node (ref "Z") (pin "DIAG0") (pinfunction "DIAG0_DIAG0") (pintype "bidirectional"))
    )
    (net (code "53") (name "/Z-MIN") (class "Default")
      (node (ref "C15") (pin "2") (pinfunction "2_2") (pintype "passive"))
      (node (ref "Z-") (pin "1") (pinfunction "1_1") (pintype "passive"))
    )
    (net (code "54") (name "/Z-STEP") (class "Default")
      (node (ref "U$1") (pin "D40") (pinfunction "D40_D40") (pintype "bidirectional"))
      (node (ref "Z") (pin "STEP") (pinfunction "STEP_STEP") (pintype "bidirectional"))
    )
    (net (code "55") (name "GND") (class "Default")
      (node (ref "C1") (pin "-") (pinfunction "-_-") (pintype "passive"))
      (node (ref "C10") (pin "-") (pinfunction "-_-") (pintype "passive"))
      (node (ref "C11") (pin "1") (pinfunction "1_1") (pintype "passive"))
      (node (ref "C12") (pin "-") (pinfunction "-_-") (pintype "passive"))
      (node (ref "C13") (pin "1") (pinfunction "1_1") (pintype "passive"))
      (node (ref "C15") (pin "1") (pinfunction "1_1") (pintype "passive"))
      (node (ref "C17") (pin "-") (pinfunction "-_-") (pintype "passive"))
      (node (ref "C2") (pin "2") (pinfunction "2_2") (pintype "passive"))
      (node (ref "C3") (pin "-") (pinfunction "-_-") (pintype "passive"))
      (node (ref "C4") (pin "-") (pinfunction "-_-") (pintype "passive"))
      (node (ref "C5") (pin "-") (pinfunction "-_-") (pintype "passive"))
      (node (ref "C6") (pin "-") (pinfunction "-_-") (pintype "passive"))
      (node (ref "C7") (pin "-") (pinfunction "-_-") (pintype "passive"))
      (node (ref "C8") (pin "-") (pinfunction "-_-") (pintype "passive"))
      (node (ref "C9") (pin "-") (pinfunction "-_-") (pintype "passive"))
      (node (ref "D2") (pin "A") (pinfunction "A_A") (pintype "passive"))
      (node (ref "D3") (pin "A") (pinfunction "A_A") (pintype "passive"))
      (node (ref "E0") (pin "GND") (pinfunction "GND_GND") (pintype "bidirectional"))
      (node (ref "E0") (pin "GND@0") (pinfunction "GND_GND@0") (pintype "bidirectional"))
      (node (ref "E1") (pin "GND") (pinfunction "GND_GND") (pintype "bidirectional"))
      (node (ref "E1") (pin "GND@0") (pinfunction "GND_GND@0") (pintype "bidirectional"))
      (node (ref "E2") (pin "GND") (pinfunction "GND_GND") (pintype "bidirectional"))
      (node (ref "E2") (pin "GND@0") (pinfunction "GND_GND@0") (pintype "bidirectional"))
      (node (ref "G12") (pin "1") (pinfunction "P_1") (pintype "passive"))
      (node (ref "GND") (pin "1") (pinfunction "P_1") (pintype "passive"))
      (node (ref "LED1") (pin "C") (pinfunction "C_C") (pintype "passive"))
      (node (ref "Q1") (pin "S") (pinfunction "S_S") (pintype "passive"))
      (node (ref "Q2") (pin "S") (pinfunction "S_S") (pintype "passive"))
      (node (ref "Q3") (pin "S") (pinfunction "S_S") (pintype "passive"))
      (node (ref "R19") (pin "2") (pinfunction "2_2") (pintype "passive"))
      (node (ref "R2") (pin "2") (pinfunction "2_2") (pintype "passive"))
      (node (ref "R27") (pin "2") (pinfunction "2_2") (pintype "passive"))
      (node (ref "R30") (pin "2") (pinfunction "2_2") (pintype "passive"))
      (node (ref "R33") (pin "2") (pinfunction "2_2") (pintype "passive"))
      (node (ref "R36") (pin "2") (pinfunction "2_2") (pintype "passive"))
      (node (ref "R4") (pin "2") (pinfunction "2_2") (pintype "passive"))
      (node (ref "R9") (pin "2") (pinfunction "2_2") (pintype "passive"))
      (node (ref "RSET") (pin "2") (pinfunction "2_2") (pintype "passive"))
      (node (ref "SERV0") (pin "1") (pinfunction "1_1") (pintype "passive"))
      (node (ref "SERV1") (pin "1") (pinfunction "1_1") (pintype "passive"))
      (node (ref "T0") (pin "2") (pinfunction "2_2") (pintype "passive"))
      (node (ref "T1") (pin "2") (pinfunction "2_2") (pintype "passive"))
      (node (ref "T2") (pin "2") (pinfunction "2_2") (pintype "passive"))
      (node (ref "T3") (pin "2") (pinfunction "2_2") (pintype "passive"))
      (node (ref "TEX0") (pin "3") (pinfunction "S_3") (pintype "passive"))
      (node (ref "TEX1") (pin "3") (pinfunction "S_3") (pintype "passive"))
      (node (ref "TEX2") (pin "3") (pinfunction "S_3") (pintype "passive"))
      (node (ref "TEX3") (pin "3") (pinfunction "S_3") (pintype "passive"))
      (node (ref "TEX4") (pin "3") (pinfunction "S_3") (pintype "passive"))
      (node (ref "U$1") (pin "GND@0") (pinfunction "GND_GND@0") (pintype "power_in"))
      (node (ref "U$1") (pin "GND@1") (pinfunction "GND_GND@1") (pintype "power_in"))
      (node (ref "U$1") (pin "GND@2") (pinfunction "GND_GND@2") (pintype "power_in"))
      (node (ref "U$1") (pin "GND@3") (pinfunction "GND_GND@3") (pintype "power_in"))
      (node (ref "U$1") (pin "GND@4") (pinfunction "GND_GND@4") (pintype "power_in"))
      (node (ref "U$2") (pin "P$1") (pinfunction "P$1_P$1") (pintype "bidirectional"))
      (node (ref "U$2") (pin "P$2") (pinfunction "P$2_P$2") (pintype "bidirectional"))
      (node (ref "X") (pin "GND") (pinfunction "GND_GND") (pintype "bidirectional"))
      (node (ref "X") (pin "GND@0") (pinfunction "GND_GND@0") (pintype "bidirectional"))
      (node (ref "X-") (pin "2") (pinfunction "2_2") (pintype "passive"))
      (node (ref "Y") (pin "GND") (pinfunction "GND_GND") (pintype "bidirectional"))
      (node (ref "Y") (pin "GND@0") (pinfunction "GND_GND@0") (pintype "bidirectional"))
      (node (ref "Y-") (pin "2") (pinfunction "2_2") (pintype "passive"))
      (node (ref "Z") (pin "GND") (pinfunction "GND_GND") (pintype "bidirectional"))
      (node (ref "Z") (pin "GND@0") (pinfunction "GND_GND@0") (pintype "bidirectional"))
      (node (ref "Z-") (pin "2") (pinfunction "2_2") (pintype "passive"))
    )
    (net (code "56") (name "Net-(+12-P)") (class "Default")
      (node (ref "+12") (pin "1") (pinfunction "P_1") (pintype "passive"))
      (node (ref "F1") (pin "P$1") (pinfunction "1_P$1") (pintype "passive"))
      (node (ref "F1") (pin "P$2") (pinfunction "1_P$2") (pintype "passive"))
      (node (ref "F1") (pin "P$3") (pinfunction "1_P$3") (pintype "passive"))
      (node (ref "F1") (pin "P$4") (pinfunction "1_P$4") (pintype "passive"))
    )
    (net (code "57") (name "Net-(+24-P)") (class "Default")
      (node (ref "+24") (pin "1") (pinfunction "P_1") (pintype "passive"))
      (node (ref "F2") (pin "P$1") (pinfunction "1_P$1") (pintype "passive"))
      (node (ref "F2") (pin "P$2") (pinfunction "1_P$2") (pintype "passive"))
      (node (ref "F2") (pin "P$3") (pinfunction "1_P$3") (pintype "passive"))
      (node (ref "F2") (pin "P$4") (pinfunction "1_P$4") (pintype "passive"))
    )
    (net (code "58") (name "Net-(EX0-Pad2)") (class "Default")
      (node (ref "EX0") (pin "2") (pinfunction "2_2") (pintype "passive"))
      (node (ref "LED9") (pin "C") (pinfunction "C_C") (pintype "passive"))
      (node (ref "TEX0") (pin "2") (pinfunction "D_2") (pintype "passive"))
      (node (ref "TEX0") (pin "4") (pinfunction "D_4") (pintype "passive"))
    )
    (net (code "59") (name "Net-(EX1-Pad2)") (class "Default")
      (node (ref "EX1") (pin "2") (pinfunction "2_2") (pintype "passive"))
      (node (ref "LED8") (pin "C") (pinfunction "C_C") (pintype "passive"))
      (node (ref "TEX1") (pin "2") (pinfunction "D_2") (pintype "passive"))
      (node (ref "TEX1") (pin "4") (pinfunction "D_4") (pintype "passive"))
    )
    (net (code "60") (name "Net-(EX2-Pad2)") (class "Default")
      (node (ref "EX2") (pin "2") (pinfunction "2_2") (pintype "passive"))
      (node (ref "LED7") (pin "C") (pinfunction "C_C") (pintype "passive"))
      (node (ref "TEX2") (pin "2") (pinfunction "D_2") (pintype "passive"))
      (node (ref "TEX2") (pin "4") (pinfunction "D_4") (pintype "passive"))
    )
    (net (code "61") (name "Net-(EX3-Pad2)") (class "Default")
      (node (ref "EX3") (pin "2") (pinfunction "2_2") (pintype "passive"))
      (node (ref "LED5") (pin "C") (pinfunction "C_C") (pintype "passive"))
      (node (ref "TEX3") (pin "2") (pinfunction "D_2") (pintype "passive"))
      (node (ref "TEX3") (pin "4") (pinfunction "D_4") (pintype "passive"))
    )
    (net (code "62") (name "Net-(EX4-Pad2)") (class "Default")
      (node (ref "EX4") (pin "2") (pinfunction "2_2") (pintype "passive"))
      (node (ref "LED6") (pin "C") (pinfunction "C_C") (pintype "passive"))
      (node (ref "TEX4") (pin "2") (pinfunction "D_2") (pintype "passive"))
      (node (ref "TEX4") (pin "4") (pinfunction "D_4") (pintype "passive"))
    )
    (net (code "63") (name "Net-(HEAT1-2)") (class "Default")
      (node (ref "HEAT1") (pin "P2") (pinfunction "2_P2") (pintype "passive"))
      (node (ref "LED10") (pin "C") (pinfunction "C_C") (pintype "passive"))
      (node (ref "Q1") (pin "D") (pinfunction "D_D") (pintype "passive"))
    )
    (net (code "64") (name "Net-(HEAT2-2)") (class "Default")
      (node (ref "HEAT2") (pin "P2") (pinfunction "2_P2") (pintype "passive"))
      (node (ref "LEDD9") (pin "C") (pinfunction "C_C") (pintype "passive"))
      (node (ref "Q2") (pin "D") (pinfunction "D_D") (pintype "passive"))
    )
    (net (code "65") (name "Net-(HEAT3-2)") (class "Default")
      (node (ref "HEAT3") (pin "P2") (pinfunction "2_P2") (pintype "passive"))
      (node (ref "LEDD8") (pin "C") (pinfunction "C_C") (pintype "passive"))
      (node (ref "Q3") (pin "D") (pinfunction "D_D") (pintype "passive"))
    )
    (net (code "66") (name "Net-(LED1-PadA)") (class "Default")
      (node (ref "LED1") (pin "A") (pinfunction "A_A") (pintype "passive"))
      (node (ref "R12") (pin "1") (pinfunction "1_1") (pintype "passive"))
    )
    (net (code "67") (name "Net-(LED5-PadA)") (class "Default")
      (node (ref "LED5") (pin "A") (pinfunction "A_A") (pintype "passive"))
      (node (ref "R20") (pin "2") (pinfunction "2_2") (pintype "passive"))
    )
    (net (code "68") (name "Net-(LED6-PadA)") (class "Default")
      (node (ref "LED6") (pin "A") (pinfunction "A_A") (pintype "passive"))
      (node (ref "R28") (pin "2") (pinfunction "2_2") (pintype "passive"))
    )
    (net (code "69") (name "Net-(LED7-PadA)") (class "Default")
      (node (ref "LED7") (pin "A") (pinfunction "A_A") (pintype "passive"))
      (node (ref "R31") (pin "2") (pinfunction "2_2") (pintype "passive"))
    )
    (net (code "70") (name "Net-(LED8-PadA)") (class "Default")
      (node (ref "LED8") (pin "A") (pinfunction "A_A") (pintype "passive"))
      (node (ref "R34") (pin "2") (pinfunction "2_2") (pintype "passive"))
    )
    (net (code "71") (name "Net-(LED9-PadA)") (class "Default")
      (node (ref "LED9") (pin "A") (pinfunction "A_A") (pintype "passive"))
      (node (ref "R37") (pin "2") (pinfunction "2_2") (pintype "passive"))
    )
    (net (code "72") (name "Net-(LED10-PadA)") (class "Default")
      (node (ref "LED10") (pin "A") (pinfunction "A_A") (pintype "passive"))
      (node (ref "R25") (pin "2") (pinfunction "2_2") (pintype "passive"))
    )
    (net (code "73") (name "Net-(LEDD8-PadA)") (class "Default")
      (node (ref "LEDD8") (pin "A") (pinfunction "A_A") (pintype "passive"))
      (node (ref "R23") (pin "2") (pinfunction "2_2") (pintype "passive"))
    )
    (net (code "74") (name "Net-(LEDD9-PadA)") (class "Default")
      (node (ref "LEDD9") (pin "A") (pinfunction "A_A") (pintype "passive"))
      (node (ref "R24") (pin "2") (pinfunction "2_2") (pintype "passive"))
    )
    (net (code "75") (name "Net-(Q1-PadG)") (class "Default")
      (node (ref "Q1") (pin "G") (pinfunction "G_G") (pintype "passive"))
      (node (ref "R13") (pin "2") (pinfunction "2_2") (pintype "passive"))
    )
    (net (code "76") (name "Net-(Q2-PadG)") (class "Default")
      (node (ref "Q2") (pin "G") (pinfunction "G_G") (pintype "passive"))
      (node (ref "R14") (pin "2") (pinfunction "2_2") (pintype "passive"))
    )
    (net (code "77") (name "Net-(Q3-PadG)") (class "Default")
      (node (ref "Q3") (pin "G") (pinfunction "G_G") (pintype "passive"))
      (node (ref "R15") (pin "2") (pinfunction "2_2") (pintype "passive"))
    )
    (net (code "78") (name "Net-(TEX0-G)") (class "Default")
      (node (ref "R35") (pin "2") (pinfunction "2_2") (pintype "passive"))
      (node (ref "TEX0") (pin "1") (pinfunction "G_1") (pintype "passive"))
    )
    (net (code "79") (name "Net-(TEX1-G)") (class "Default")
      (node (ref "R32") (pin "2") (pinfunction "2_2") (pintype "passive"))
      (node (ref "TEX1") (pin "1") (pinfunction "G_1") (pintype "passive"))
    )
    (net (code "80") (name "Net-(TEX2-G)") (class "Default")
      (node (ref "R29") (pin "2") (pinfunction "2_2") (pintype "passive"))
      (node (ref "TEX2") (pin "1") (pinfunction "G_1") (pintype "passive"))
    )
    (net (code "81") (name "Net-(TEX3-G)") (class "Default")
      (node (ref "R18") (pin "2") (pinfunction "2_2") (pintype "passive"))
      (node (ref "TEX3") (pin "1") (pinfunction "G_1") (pintype "passive"))
    )
    (net (code "82") (name "Net-(TEX4-G)") (class "Default")
      (node (ref "R26") (pin "2") (pinfunction "2_2") (pintype "passive"))
      (node (ref "TEX4") (pin "1") (pinfunction "G_1") (pintype "passive"))
    )
    (net (code "83") (name "VCC") (class "Default")
      (node (ref "E0") (pin "VDD") (pinfunction "VIO_VDD") (pintype "bidirectional"))
      (node (ref "E1") (pin "VDD") (pinfunction "VIO_VDD") (pintype "bidirectional"))
      (node (ref "E2") (pin "VDD") (pinfunction "VIO_VDD") (pintype "bidirectional"))
      (node (ref "R1") (pin "2") (pinfunction "2_2") (pintype "passive"))
      (node (ref "R10") (pin "1") (pinfunction "1_1") (pintype "passive"))
      (node (ref "R11") (pin "2") (pinfunction "2_2") (pintype "passive"))
      (node (ref "R16") (pin "1") (pinfunction "1_1") (pintype "passive"))
      (node (ref "R17") (pin "2") (pinfunction "2_2") (pintype "passive"))
      (node (ref "R20") (pin "1") (pinfunction "1_1") (pintype "passive"))
      (node (ref "R28") (pin "1") (pinfunction "1_1") (pintype "passive"))
      (node (ref "R3") (pin "1") (pinfunction "1_1") (pintype "passive"))
      (node (ref "R31") (pin "1") (pinfunction "1_1") (pintype "passive"))
      (node (ref "R34") (pin "1") (pinfunction "1_1") (pintype "passive"))
      (node (ref "R37") (pin "1") (pinfunction "1_1") (pintype "passive"))
      (node (ref "R5") (pin "1") (pinfunction "1_1") (pintype "passive"))
      (node (ref "R6") (pin "1") (pinfunction "1_1") (pintype "passive"))
      (node (ref "R7") (pin "2") (pinfunction "2_2") (pintype "passive"))
      (node (ref "R8") (pin "1") (pinfunction "1_1") (pintype "passive"))
      (node (ref "SERV0") (pin "2") (pinfunction "2_2") (pintype "passive"))
      (node (ref "SERV1") (pin "2") (pinfunction "2_2") (pintype "passive"))
      (node (ref "U$1") (pin "5V@0") (pinfunction "5V_5V@0") (pintype "power_in"))
      (node (ref "U$1") (pin "5V@1") (pinfunction "5V_5V@1") (pintype "power_in"))
      (node (ref "U$1") (pin "5V@2") (pinfunction "5V_5V@2") (pintype "power_in"))
      (node (ref "X") (pin "VDD") (pinfunction "VIO_VDD") (pintype "bidirectional"))
      (node (ref "X-") (pin "3") (pinfunction "3_3") (pintype "passive"))
      (node (ref "Y") (pin "VDD") (pinfunction "VIO_VDD") (pintype "bidirectional"))
      (node (ref "Y-") (pin "3") (pinfunction "3_3") (pintype "passive"))
      (node (ref "Z") (pin "VDD") (pinfunction "VIO_VDD") (pintype "bidirectional"))
      (node (ref "Z-") (pin "3") (pinfunction "3_3") (pintype "passive"))
    )
    (net (code "84") (name "unconnected-(E0-M1A-Pad1A)") (class "Default")
      (node (ref "E0") (pin "1A") (pinfunction "M1A_1A") (pintype "bidirectional"))
    )
    (net (code "85") (name "unconnected-(E0-M1B-Pad1B)") (class "Default")
      (node (ref "E0") (pin "1B") (pinfunction "M1B_1B") (pintype "bidirectional"))
    )
    (net (code "86") (name "unconnected-(E0-M2A-Pad2A)") (class "Default")
      (node (ref "E0") (pin "2A") (pinfunction "M2A_2A") (pintype "bidirectional"))
    )
    (net (code "87") (name "unconnected-(E0-M2B-Pad2B)") (class "Default")
      (node (ref "E0") (pin "2B") (pinfunction "M2B_2B") (pintype "bidirectional"))
    )
    (net (code "88") (name "unconnected-(E1-M1A-Pad1A)") (class "Default")
      (node (ref "E1") (pin "1A") (pinfunction "M1A_1A") (pintype "bidirectional"))
    )
    (net (code "89") (name "unconnected-(E1-M1B-Pad1B)") (class "Default")
      (node (ref "E1") (pin "1B") (pinfunction "M1B_1B") (pintype "bidirectional"))
    )
    (net (code "90") (name "unconnected-(E1-M2A-Pad2A)") (class "Default")
      (node (ref "E1") (pin "2A") (pinfunction "M2A_2A") (pintype "bidirectional"))
    )
    (net (code "91") (name "unconnected-(E1-M2B-Pad2B)") (class "Default")
      (node (ref "E1") (pin "2B") (pinfunction "M2B_2B") (pintype "bidirectional"))
    )
    (net (code "92") (name "unconnected-(E2-M1A-Pad1A)") (class "Default")
      (node (ref "E2") (pin "1A") (pinfunction "M1A_1A") (pintype "bidirectional"))
    )
    (net (code "93") (name "unconnected-(E2-M1B-Pad1B)") (class "Default")
      (node (ref "E2") (pin "1B") (pinfunction "M1B_1B") (pintype "bidirectional"))
    )
    (net (code "94") (name "unconnected-(E2-M2A-Pad2A)") (class "Default")
      (node (ref "E2") (pin "2A") (pinfunction "M2A_2A") (pintype "bidirectional"))
    )
    (net (code "95") (name "unconnected-(E2-M2B-Pad2B)") (class "Default")
      (node (ref "E2") (pin "2B") (pinfunction "M2B_2B") (pintype "bidirectional"))
    )
    (net (code "96") (name "unconnected-(U$1-PadA11)") (class "Default")
      (node (ref "U$1") (pin "A11") (pinfunction "A11_A11") (pintype "bidirectional"))
    )
    (net (code "97") (name "unconnected-(U$1-PadD7)") (class "Default")
      (node (ref "U$1") (pin "D7") (pinfunction "D7_D7") (pintype "bidirectional"))
    )
    (net (code "98") (name "unconnected-(U$1-PadD8)") (class "Default")
      (node (ref "U$1") (pin "D8") (pinfunction "D8_D8") (pintype "bidirectional"))
    )
    (net (code "99") (name "unconnected-(U$1-PadD9)") (class "Default")
      (node (ref "U$1") (pin "D9") (pinfunction "D9_D9") (pintype "bidirectional"))
    )
    (net (code "100") (name "unconnected-(U$1-PadD10)") (class "Default")
      (node (ref "U$1") (pin "D10") (pinfunction "D10_D10") (pintype "bidirectional"))
    )
    (net (code "101") (name "unconnected-(U$1-PadD32)") (class "Default")
      (node (ref "U$1") (pin "D32") (pinfunction "D32_D32") (pintype "bidirectional"))
    )
    (net (code "102") (name "unconnected-(U$1-PadD33)") (class "Default")
      (node (ref "U$1") (pin "D33") (pinfunction "D33_D33") (pintype "bidirectional"))
    )
    (net (code "103") (name "unconnected-(U$1-PadD34)") (class "Default")
      (node (ref "U$1") (pin "D34") (pinfunction "D34_D34") (pintype "bidirectional"))
    )
    (net (code "104") (name "unconnected-(U$1-PadD35)") (class "Default")
      (node (ref "U$1") (pin "D35") (pinfunction "D35_D35") (pintype "bidirectional"))
    )
    (net (code "105") (name "unconnected-(U$1-PadD37)") (class "Default")
      (node (ref "U$1") (pin "D37") (pinfunction "D37_D37") (pintype "bidirectional"))
    )
    (net (code "106") (name "unconnected-(U$1-PadD41)") (class "Default")
      (node (ref "U$1") (pin "D41") (pinfunction "D41_D41") (pintype "bidirectional"))
    )
    (net (code "107") (name "unconnected-(U$1-PadD43)") (class "Default")
      (node (ref "U$1") (pin "D43") (pinfunction "D43_D43") (pintype "bidirectional"))
    )
    (net (code "108") (name "unconnected-(U$1-PadD47)") (class "Default")
      (node (ref "U$1") (pin "D47") (pinfunction "D47_D47") (pintype "bidirectional"))
    )
    (net (code "109") (name "unconnected-(U$1-PadD48)") (class "Default")
      (node (ref "U$1") (pin "D48") (pinfunction "D48_D48") (pintype "bidirectional"))
    )
    (net (code "110") (name "unconnected-(U$1-PadD49)") (class "Default")
      (node (ref "U$1") (pin "D49") (pinfunction "D49_D49") (pintype "bidirectional"))
    )
    (net (code "111") (name "unconnected-(U$1-PadD50)") (class "Default")
      (node (ref "U$1") (pin "D50") (pinfunction "D50_D50") (pintype "bidirectional"))
    )
    (net (code "112") (name "unconnected-(U$1-PadD51)") (class "Default")
      (node (ref "U$1") (pin "D51") (pinfunction "D51_D51") (pintype "bidirectional"))
    )
    (net (code "113") (name "unconnected-(U$1-PadD52)") (class "Default")
      (node (ref "U$1") (pin "D52") (pinfunction "D52_D52") (pintype "bidirectional"))
    )
    (net (code "114") (name "unconnected-(U$1-PadD53)") (class "Default")
      (node (ref "U$1") (pin "D53") (pinfunction "D53_D53") (pintype "bidirectional"))
    )
    (net (code "115") (name "unconnected-(U$1-PadRX)") (class "Default")
      (node (ref "U$1") (pin "RX") (pinfunction "RX_RX") (pintype "bidirectional"))
    )
    (net (code "116") (name "unconnected-(U$1-PadTX)") (class "Default")
      (node (ref "U$1") (pin "TX") (pinfunction "TX_TX") (pintype "bidirectional"))
    )
    (net (code "117") (name "unconnected-(U$1-PadVIN)") (class "Default")
      (node (ref "U$1") (pin "VIN") (pinfunction "VIN_VIN") (pintype "input"))
    )
    (net (code "118") (name "unconnected-(X-M1A-Pad1A)") (class "Default")
      (node (ref "X") (pin "1A") (pinfunction "M1A_1A") (pintype "bidirectional"))
    )
    (net (code "119") (name "unconnected-(X-M1B-Pad1B)") (class "Default")
      (node (ref "X") (pin "1B") (pinfunction "M1B_1B") (pintype "bidirectional"))
    )
    (net (code "120") (name "unconnected-(X-M2A-Pad2A)") (class "Default")
      (node (ref "X") (pin "2A") (pinfunction "M2A_2A") (pintype "bidirectional"))
    )
    (net (code "121") (name "unconnected-(X-M2B-Pad2B)") (class "Default")
      (node (ref "X") (pin "2B") (pinfunction "M2B_2B") (pintype "bidirectional"))
    )
    (net (code "122") (name "unconnected-(Y-M1A-Pad1A)") (class "Default")
      (node (ref "Y") (pin "1A") (pinfunction "M1A_1A") (pintype "bidirectional"))
    )
    (net (code "123") (name "unconnected-(Y-M1B-Pad1B)") (class "Default")
      (node (ref "Y") (pin "1B") (pinfunction "M1B_1B") (pintype "bidirectional"))
    )
    (net (code "124") (name "unconnected-(Y-M2A-Pad2A)") (class "Default")
      (node (ref "Y") (pin "2A") (pinfunction "M2A_2A") (pintype "bidirectional"))
    )
    (net (code "125") (name "unconnected-(Y-M2B-Pad2B)") (class "Default")
      (node (ref "Y") (pin "2B") (pinfunction "M2B_2B") (pintype "bidirectional"))
    )
    (net (code "126") (name "unconnected-(Z-M1A-Pad1A)") (class "Default")
      (node (ref "Z") (pin "1A") (pinfunction "M1A_1A") (pintype "bidirectional"))
    )
    (net (code "127") (name "unconnected-(Z-M1B-Pad1B)") (class "Default")
      (node (ref "Z") (pin "1B") (pinfunction "M1B_1B") (pintype "bidirectional"))
    )
    (net (code "128") (name "unconnected-(Z-M2A-Pad2A)") (class "Default")
      (node (ref "Z") (pin "2A") (pinfunction "M2A_2A") (pintype "bidirectional"))
    )
    (net (code "129") (name "unconnected-(Z-M2B-Pad2B)") (class "Default")
      (node (ref "Z") (pin "2B") (pinfunction "M2B_2B") (pintype "bidirectional"))
    )
  )
)
